# 3_LED_Target.net
KiCad netlist of a schematic drawn in EAGLE
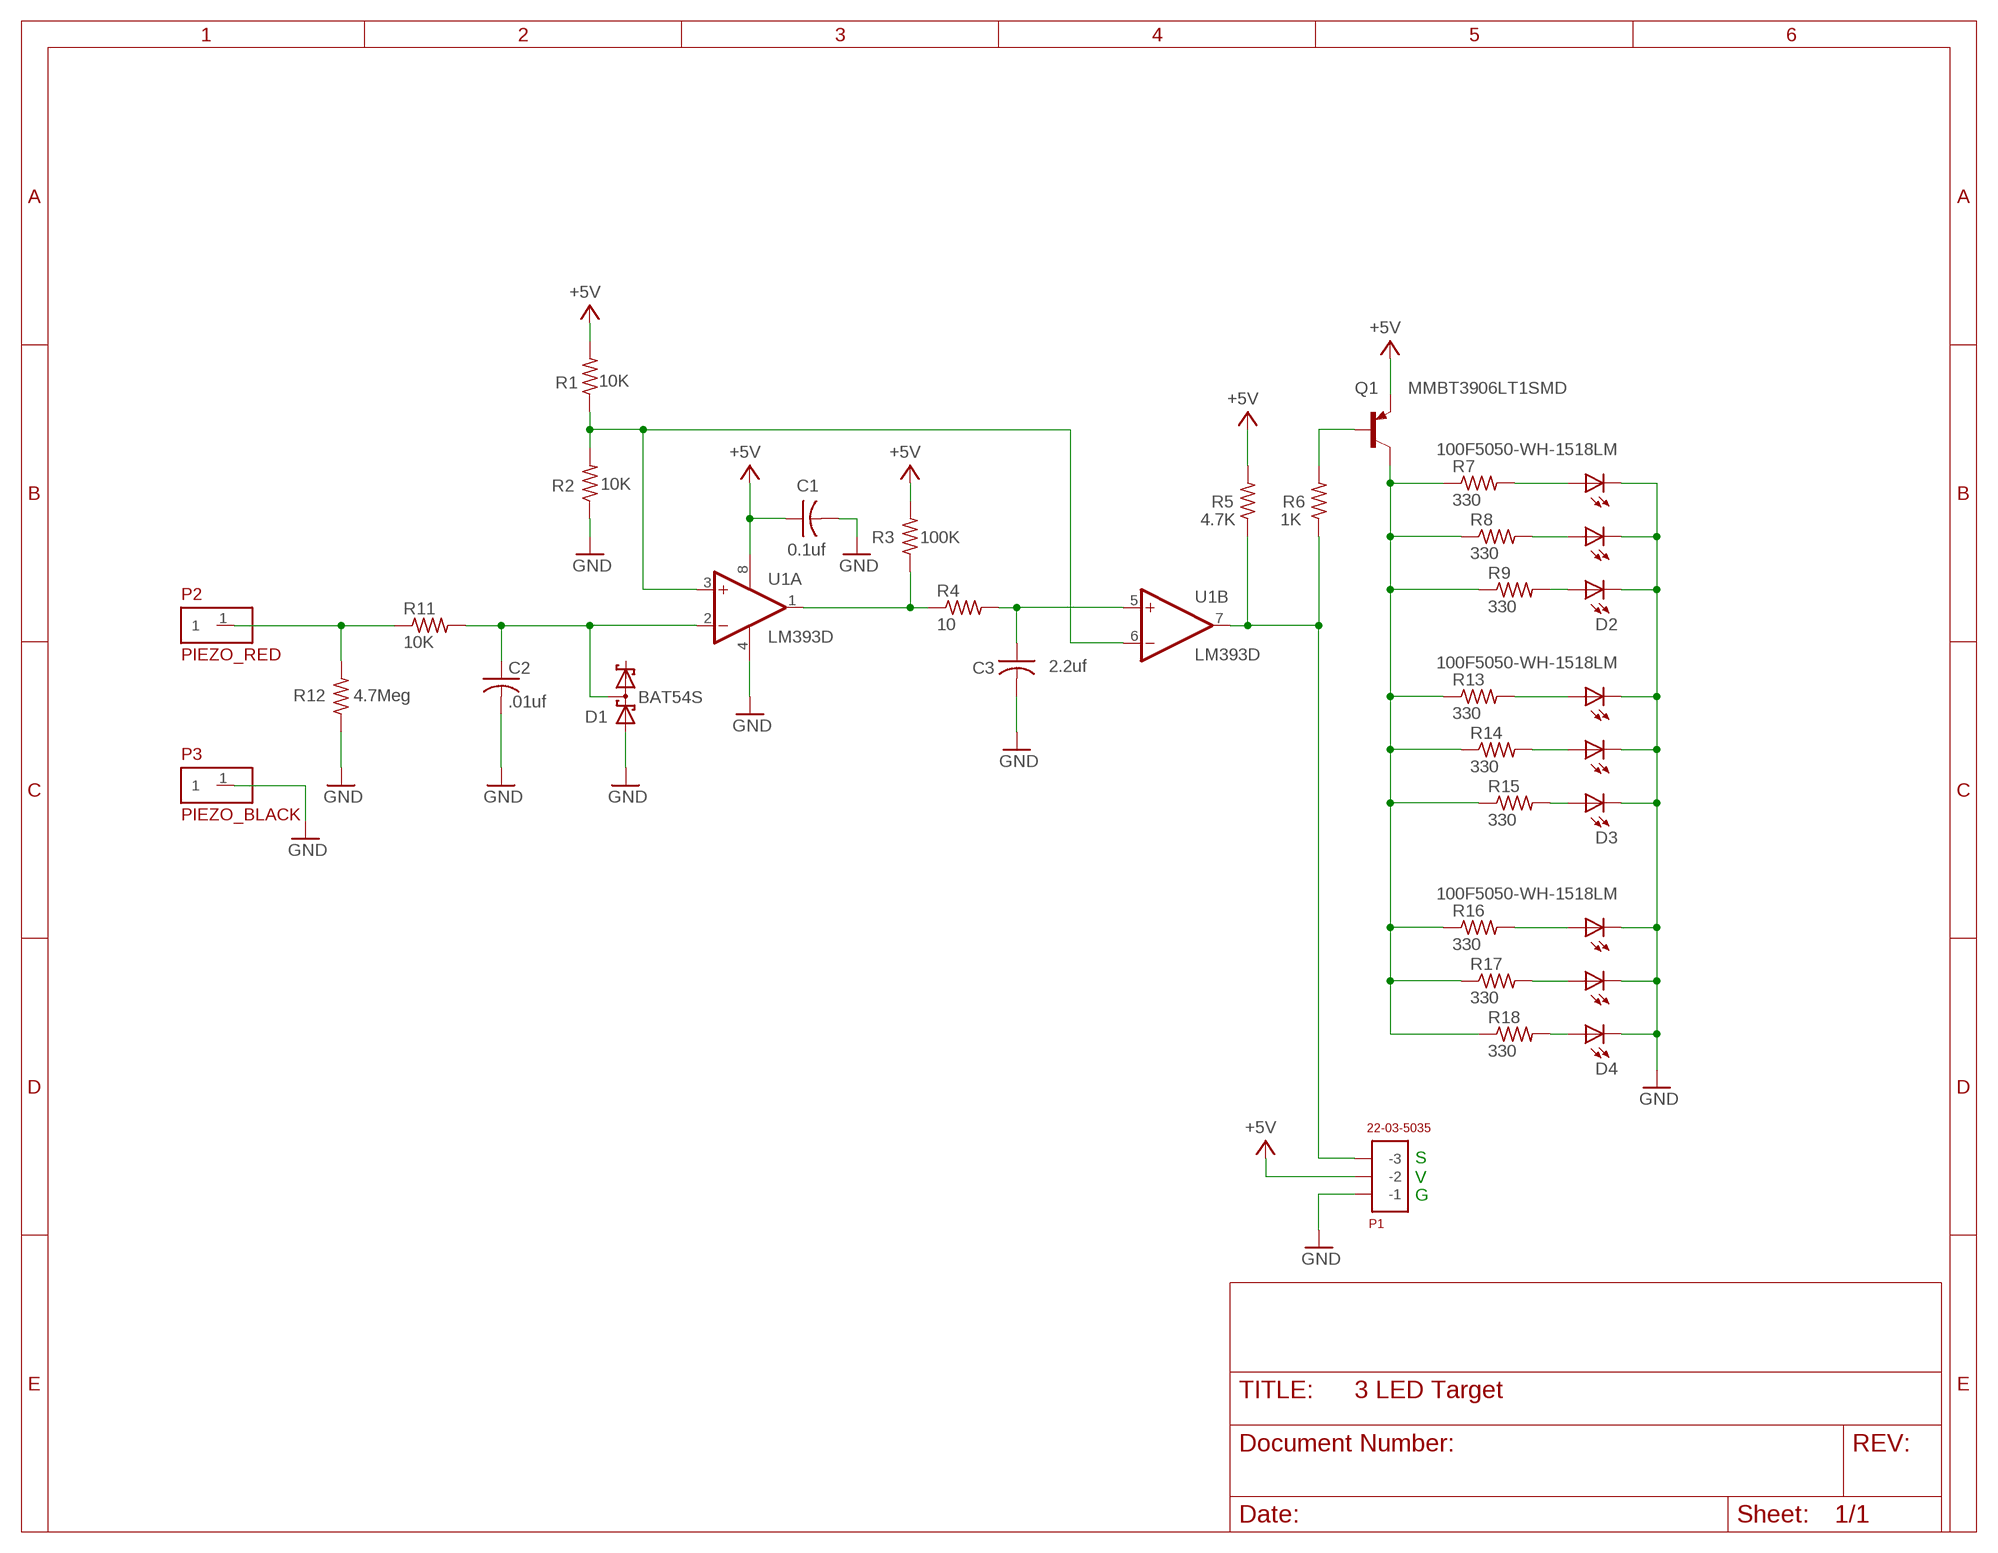
[diagram p0: schematic, sheet 1]

(export (version "E")
  (design (tool "Eeschema 10.0.6"))
  (components
    (comp (ref "C1")
      (value "0.1uf")
      (footprint "eagle-import:C0603")
      (libsource (lib "eagle-import") (part "C-USC0603"))
    )
    (comp (ref "C2")
      (value ".01uf")
      (footprint "eagle-import:C0603")
      (libsource (lib "eagle-import") (part "C-USC0603"))
    )
    (comp (ref "C3")
      (value "2.2uf")
      (footprint "eagle-import:C1206")
      (libsource (lib "eagle-import") (part "C-USC1206"))
    )
    (comp (ref "D1")
      (value "BAT54S")
      (footprint "eagle-import:SOT23")
      (libsource (lib "eagle-import") (part "BAT54S"))
    )
    (comp (ref "D2")
      (value "100F5050-WH-1518LM")
      (footprint "eagle-import:LED5050")
      (libsource (lib "eagle-import") (part "100F5050-WH-1518LM"))
    )
    (comp (ref "D3")
      (value "100F5050-WH-1518LM")
      (footprint "eagle-import:LED5050")
      (libsource (lib "eagle-import") (part "100F5050-WH-1518LM"))
    )
    (comp (ref "D4")
      (value "100F5050-WH-1518LM")
      (footprint "eagle-import:LED5050")
      (libsource (lib "eagle-import") (part "100F5050-WH-1518LM"))
    )
    (comp (ref "P1")
      (value "22-03-5035")
      (footprint "eagle-import:MOLEX3_STRAIGHT")
      (libsource (lib "eagle-import") (part "22-03-5035"))
    )
    (comp (ref "P2")
      (value "PIEZO_RED")
      (footprint "eagle-import:PADHOLE")
      (libsource (lib "eagle-import") (part "PINHOLE"))
    )
    (comp (ref "P3")
      (value "PIEZO_BLACK")
      (footprint "eagle-import:PADHOLE")
      (libsource (lib "eagle-import") (part "PINHOLE"))
    )
    (comp (ref "Q1")
      (value "MMBT3906LT1SMD")
      (footprint "eagle-import:SOT23-BEC")
      (libsource (lib "eagle-import") (part "MMBT3906SMDLT1"))
    )
    (comp (ref "R1")
      (value "10K")
      (footprint "eagle-import:R0603")
      (libsource (lib "eagle-import") (part "R-US_R0603"))
    )
    (comp (ref "R2")
      (value "10K")
      (footprint "eagle-import:R0603")
      (libsource (lib "eagle-import") (part "R-US_R0603"))
    )
    (comp (ref "R3")
      (value "100K")
      (footprint "eagle-import:R0603")
      (libsource (lib "eagle-import") (part "R-US_R0603"))
    )
    (comp (ref "R4")
      (value "10")
      (footprint "eagle-import:R0603")
      (libsource (lib "eagle-import") (part "R-US_R0603"))
    )
    (comp (ref "R5")
      (value "4.7K")
      (footprint "eagle-import:R0603")
      (libsource (lib "eagle-import") (part "R-US_R0603"))
    )
    (comp (ref "R6")
      (value "1K")
      (footprint "eagle-import:R0603")
      (libsource (lib "eagle-import") (part "R-US_R0603"))
    )
    (comp (ref "R7")
      (value "330")
      (footprint "eagle-import:R0603")
      (libsource (lib "eagle-import") (part "R-US_R0603"))
    )
    (comp (ref "R8")
      (value "330")
      (footprint "eagle-import:R0603")
      (libsource (lib "eagle-import") (part "R-US_R0603"))
    )
    (comp (ref "R9")
      (value "330")
      (footprint "eagle-import:R0603")
      (libsource (lib "eagle-import") (part "R-US_R0603"))
    )
    (comp (ref "R11")
      (value "10K")
      (footprint "eagle-import:R0603")
      (libsource (lib "eagle-import") (part "R-US_R0603"))
    )
    (comp (ref "R12")
      (value "4.7Meg")
      (footprint "eagle-import:R0603")
      (libsource (lib "eagle-import") (part "R-US_R0603"))
    )
    (comp (ref "R13")
      (value "330")
      (footprint "eagle-import:R0603")
      (libsource (lib "eagle-import") (part "R-US_R0603"))
    )
    (comp (ref "R14")
      (value "330")
      (footprint "eagle-import:R0603")
      (libsource (lib "eagle-import") (part "R-US_R0603"))
    )
    (comp (ref "R15")
      (value "330")
      (footprint "eagle-import:R0603")
      (libsource (lib "eagle-import") (part "R-US_R0603"))
    )
    (comp (ref "R16")
      (value "330")
      (footprint "eagle-import:R0603")
      (libsource (lib "eagle-import") (part "R-US_R0603"))
    )
    (comp (ref "R17")
      (value "330")
      (footprint "eagle-import:R0603")
      (libsource (lib "eagle-import") (part "R-US_R0603"))
    )
    (comp (ref "R18")
      (value "330")
      (footprint "eagle-import:R0603")
      (libsource (lib "eagle-import") (part "R-US_R0603"))
    )
    (comp (ref "U1")
      (value "LM393D")
      (footprint "eagle-import:SO08")
      (libsource (lib "eagle-import") (part "LM393D"))
    )
  )
  (nets
    (net (code "1") (name "+5V") (class "Default")
      (node (ref "C1") (pin "1") (pinfunction "1_1") (pintype "passive"))
      (node (ref "P1") (pin "2") (pinfunction "-2_2") (pintype "bidirectional"))
      (node (ref "Q1") (pin "E") (pinfunction "E_E") (pintype "passive"))
      (node (ref "R1") (pin "2") (pinfunction "2_2") (pintype "passive"))
      (node (ref "R3") (pin "2") (pinfunction "2_2") (pintype "passive"))
      (node (ref "R5") (pin "2") (pinfunction "2_2") (pintype "passive"))
      (node (ref "U1") (pin "8") (pinfunction "V+_8") (pintype "power_in"))
    )
    (net (code "2") (name "GND") (class "Default")
      (node (ref "C1") (pin "2") (pinfunction "2_2") (pintype "passive"))
      (node (ref "C2") (pin "2") (pinfunction "2_2") (pintype "passive"))
      (node (ref "C3") (pin "2") (pinfunction "2_2") (pintype "passive"))
      (node (ref "D1") (pin "1") (pinfunction "A1_1") (pintype "passive"))
      (node (ref "D2") (pin "4") (pinfunction "C2_4") (pintype "passive"))
      (node (ref "D2") (pin "5") (pinfunction "C1_5") (pintype "passive"))
      (node (ref "D2") (pin "6") (pinfunction "C_6") (pintype "passive"))
      (node (ref "D3") (pin "4") (pinfunction "C2_4") (pintype "passive"))
      (node (ref "D3") (pin "5") (pinfunction "C1_5") (pintype "passive"))
      (node (ref "D3") (pin "6") (pinfunction "C_6") (pintype "passive"))
      (node (ref "D4") (pin "4") (pinfunction "C2_4") (pintype "passive"))
      (node (ref "D4") (pin "5") (pinfunction "C1_5") (pintype "passive"))
      (node (ref "D4") (pin "6") (pinfunction "C_6") (pintype "passive"))
      (node (ref "P1") (pin "1") (pinfunction "-1_1") (pintype "bidirectional"))
      (node (ref "P3") (pin "1") (pinfunction "1_1") (pintype "bidirectional"))
      (node (ref "R12") (pin "1") (pinfunction "1_1") (pintype "passive"))
      (node (ref "R2") (pin "1") (pinfunction "1_1") (pintype "passive"))
      (node (ref "U1") (pin "4") (pinfunction "V-_4") (pintype "power_in"))
    )
    (net (code "3") (name "Net-(D1-C1A2)") (class "Default")
      (node (ref "C2") (pin "1") (pinfunction "1_1") (pintype "passive"))
      (node (ref "D1") (pin "3") (pinfunction "C1A2_3") (pintype "passive"))
      (node (ref "R11") (pin "2") (pinfunction "2_2") (pintype "passive"))
      (node (ref "U1") (pin "2") (pinfunction "-IN_2") (pintype "input"))
    )
    (net (code "4") (name "Net-(D2-A)") (class "Default")
      (node (ref "D2") (pin "1") (pinfunction "A_1") (pintype "passive"))
      (node (ref "R7") (pin "2") (pinfunction "2_2") (pintype "passive"))
    )
    (net (code "5") (name "Net-(D2-A1)") (class "Default")
      (node (ref "D2") (pin "2") (pinfunction "A1_2") (pintype "passive"))
      (node (ref "R8") (pin "2") (pinfunction "2_2") (pintype "passive"))
    )
    (net (code "6") (name "Net-(D2-A2)") (class "Default")
      (node (ref "D2") (pin "3") (pinfunction "A2_3") (pintype "passive"))
      (node (ref "R9") (pin "2") (pinfunction "2_2") (pintype "passive"))
    )
    (net (code "7") (name "Net-(D3-A)") (class "Default")
      (node (ref "D3") (pin "1") (pinfunction "A_1") (pintype "passive"))
      (node (ref "R13") (pin "2") (pinfunction "2_2") (pintype "passive"))
    )
    (net (code "8") (name "Net-(D3-A1)") (class "Default")
      (node (ref "D3") (pin "2") (pinfunction "A1_2") (pintype "passive"))
      (node (ref "R14") (pin "2") (pinfunction "2_2") (pintype "passive"))
    )
    (net (code "9") (name "Net-(D3-A2)") (class "Default")
      (node (ref "D3") (pin "3") (pinfunction "A2_3") (pintype "passive"))
      (node (ref "R15") (pin "2") (pinfunction "2_2") (pintype "passive"))
    )
    (net (code "10") (name "Net-(D4-A)") (class "Default")
      (node (ref "D4") (pin "1") (pinfunction "A_1") (pintype "passive"))
      (node (ref "R16") (pin "2") (pinfunction "2_2") (pintype "passive"))
    )
    (net (code "11") (name "Net-(D4-A1)") (class "Default")
      (node (ref "D4") (pin "2") (pinfunction "A1_2") (pintype "passive"))
      (node (ref "R17") (pin "2") (pinfunction "2_2") (pintype "passive"))
    )
    (net (code "12") (name "Net-(D4-A2)") (class "Default")
      (node (ref "D4") (pin "3") (pinfunction "A2_3") (pintype "passive"))
      (node (ref "R18") (pin "2") (pinfunction "2_2") (pintype "passive"))
    )
    (net (code "13") (name "Net-(P1--3)") (class "Default")
      (node (ref "P1") (pin "3") (pinfunction "-3_3") (pintype "bidirectional"))
      (node (ref "R5") (pin "1") (pinfunction "1_1") (pintype "passive"))
      (node (ref "R6") (pin "1") (pinfunction "1_1") (pintype "passive"))
      (node (ref "U1") (pin "7") (pinfunction "OUT_7") (pintype "output"))
    )
    (net (code "14") (name "Net-(P2-Pad1)") (class "Default")
      (node (ref "P2") (pin "1") (pinfunction "1_1") (pintype "bidirectional"))
      (node (ref "R11") (pin "1") (pinfunction "1_1") (pintype "passive"))
      (node (ref "R12") (pin "2") (pinfunction "2_2") (pintype "passive"))
    )
    (net (code "15") (name "Net-(Q1-PadB)") (class "Default")
      (node (ref "Q1") (pin "B") (pinfunction "B_B") (pintype "passive"))
      (node (ref "R6") (pin "2") (pinfunction "2_2") (pintype "passive"))
    )
    (net (code "16") (name "Net-(Q1-PadC)") (class "Default")
      (node (ref "Q1") (pin "C") (pinfunction "C_C") (pintype "passive"))
      (node (ref "R13") (pin "1") (pinfunction "1_1") (pintype "passive"))
      (node (ref "R14") (pin "1") (pinfunction "1_1") (pintype "passive"))
      (node (ref "R15") (pin "1") (pinfunction "1_1") (pintype "passive"))
      (node (ref "R16") (pin "1") (pinfunction "1_1") (pintype "passive"))
      (node (ref "R17") (pin "1") (pinfunction "1_1") (pintype "passive"))
      (node (ref "R18") (pin "1") (pinfunction "1_1") (pintype "passive"))
      (node (ref "R7") (pin "1") (pinfunction "1_1") (pintype "passive"))
      (node (ref "R8") (pin "1") (pinfunction "1_1") (pintype "passive"))
      (node (ref "R9") (pin "1") (pinfunction "1_1") (pintype "passive"))
    )
    (net (code "17") (name "Net-(U1A-+IN)") (class "Default")
      (node (ref "R1") (pin "1") (pinfunction "1_1") (pintype "passive"))
      (node (ref "R2") (pin "2") (pinfunction "2_2") (pintype "passive"))
      (node (ref "U1") (pin "3") (pinfunction "+IN_3") (pintype "input"))
      (node (ref "U1") (pin "6") (pinfunction "-IN_6") (pintype "input"))
    )
    (net (code "18") (name "Net-(U1A-OUT)") (class "Default")
      (node (ref "R3") (pin "1") (pinfunction "1_1") (pintype "passive"))
      (node (ref "R4") (pin "1") (pinfunction "1_1") (pintype "passive"))
      (node (ref "U1") (pin "1") (pinfunction "OUT_1") (pintype "output"))
    )
    (net (code "19") (name "Net-(U1B-+IN)") (class "Default")
      (node (ref "C3") (pin "1") (pinfunction "1_1") (pintype "passive"))
      (node (ref "R4") (pin "2") (pinfunction "2_2") (pintype "passive"))
      (node (ref "U1") (pin "5") (pinfunction "+IN_5") (pintype "input"))
    )
    (net (code "20") (name "unconnected-(D1-C2-Pad2)") (class "Default")
      (node (ref "D1") (pin "2") (pinfunction "C2_2") (pintype "passive"))
    )
  )
)
